# buck_chw_v3_0.net
KiCad netlist of a schematic drawn in Altium Designer
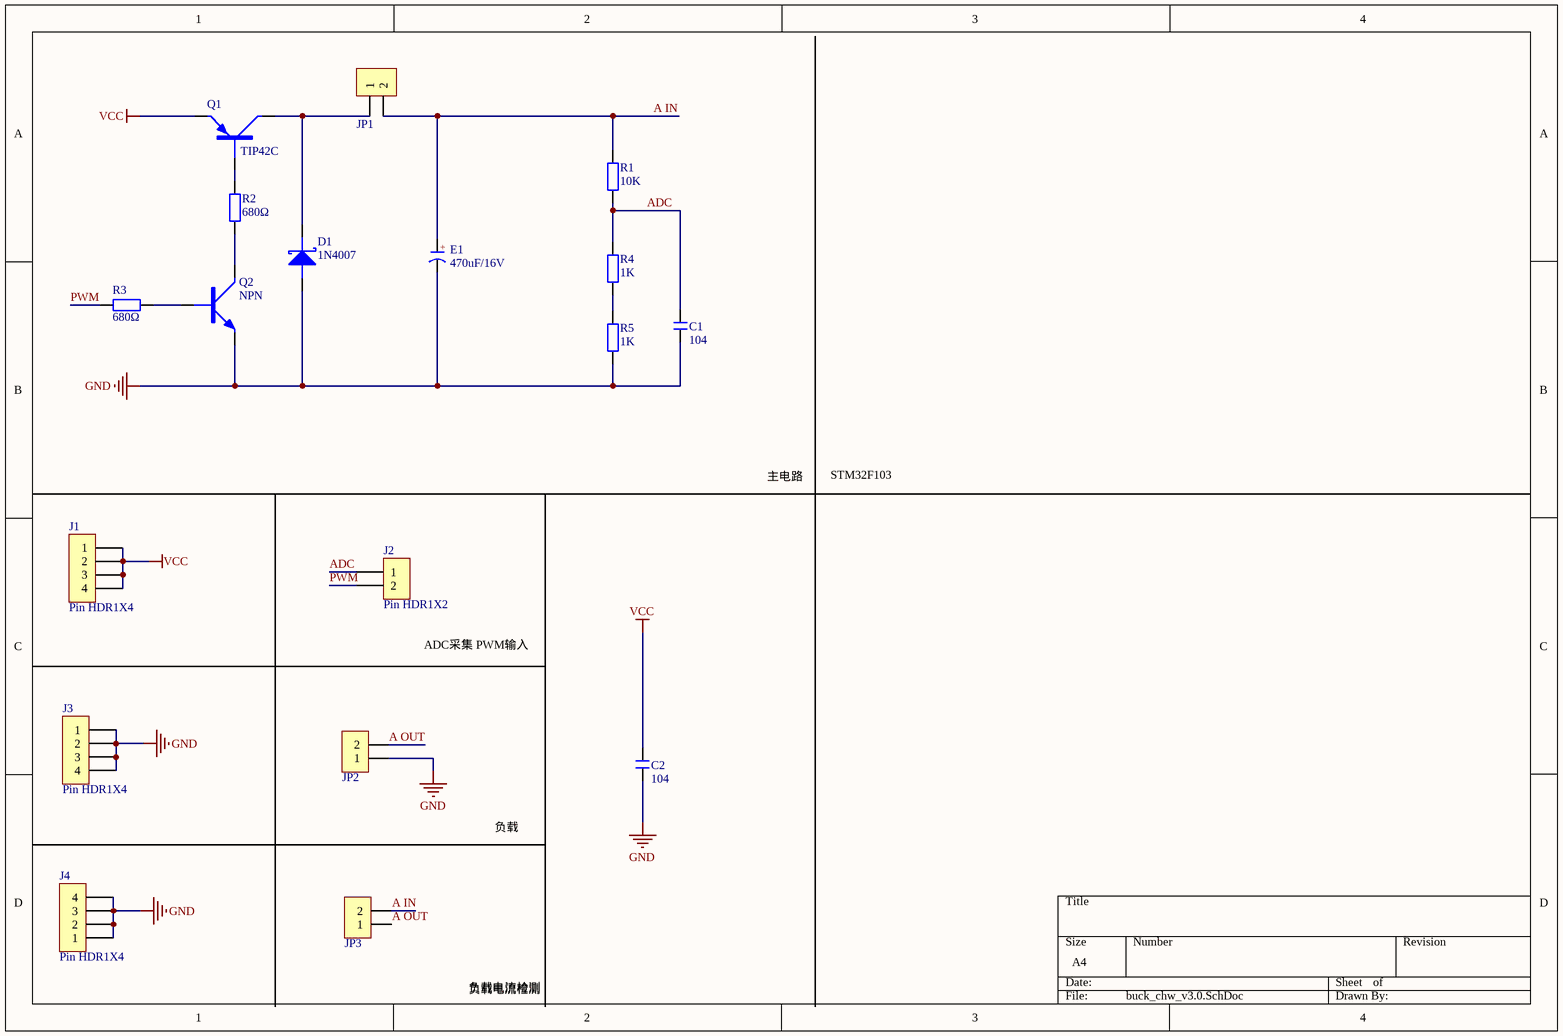
[diagram p0: buck_chw_v3.0.SchDoc]

(export (version "E")
  (design (tool "Eeschema 10.0.6"))
  (components
    (comp (ref "C1")
      (value "104")
      (footprint "CC 1.8*3.6")
      (description "直插瓷片电容")
      (fields (field (name "版权归属") "源创客"))
      (libsource (lib "3.1   - 电阻-电容-电感") (part "C-CC"))
    )
    (comp (ref "C2")
      (value "104")
      (footprint "CC 1.8*3.6")
      (description "直插瓷片电容")
      (fields (field (name "版权归属") "源创客"))
      (libsource (lib "3.1   - 电阻-电容-电感") (part "C-CC"))
    )
    (comp (ref "D1")
      (value "1N4007")
      (footprint "DO-15")
      (description "肖特基二极管")
      (libsource (lib "二极管") (part "DIODE SCHOTTKY"))
    )
    (comp (ref "E1")
      (value "470uF/16V")
      (footprint "CAP 1.5*4*8")
      (description "直插电解电容")
      (fields (field (name "版权归属") "源创客"))
      (libsource (lib "3.1   - 电阻-电容-电感") (part "C-CAP"))
    )
    (comp (ref "J1")
      (value "Pin HDR1X4")
      (footprint "Pin HDR1X4/2.54mm-S")
      (libsource (lib "") (part "Pin HDR1X4_1"))
    )
    (comp (ref "J2")
      (value "Pin HDR1X2")
      (footprint "Pin HDR1X2/2.54mm-S")
      (libsource (lib "排针") (part "Pin HDR1X2"))
    )
    (comp (ref "J3")
      (value "Pin HDR1X4")
      (footprint "Pin HDR1X4/2.54mm-S")
      (libsource (lib "") (part "Pin HDR1X4_1"))
    )
    (comp (ref "J4")
      (value "Pin HDR1X4")
      (footprint "Pin HDR1X4/2.54mm-S")
      (libsource (lib "排针") (part "Pin HDR1X4"))
    )
    (comp (ref "JP1")
      (value "HDR-1X2")
      (footprint "KF301-5.0-2P")
      (description "2P接插件")
      (fields (field (name "版权归属") "源创客"))
      (libsource (lib "") (part "Header 2_1"))
    )
    (comp (ref "JP2")
      (value "HDR-1X2")
      (footprint "KF301-5.0-2P")
      (description "2P接插件")
      (fields (field (name "版权归属") "源创客"))
      (libsource (lib "4.9   - 接插件-脚距5.0") (part "Header 2"))
    )
    (comp (ref "JP3")
      (value "HDR-1X2")
      (footprint "KF301-5.0-2P")
      (description "2P接插件")
      (fields (field (name "版权归属") "源创客"))
      (libsource (lib "4.9   - 接插件-脚距5.0") (part "Header 2"))
    )
    (comp (ref "Q1")
      (value "TIP42C")
      (footprint "Fe-HDR1X3/2.54-S")
      (description "PNP三极管")
      (libsource (lib "三极管") (part "PNP"))
    )
    (comp (ref "Q2")
      (value "NPN")
      (footprint "HDR2.54-Y-LI-3P")
      (description "NPN三极管")
      (libsource (lib "轻触开关") (part "NPN"))
    )
    (comp (ref "R1")
      (value "10K")
      (footprint "RS 1/4W")
      (description "直插色环电阻")
      (fields (field (name "版权归属") "源创客"))
      (libsource (lib "3.1   - 电阻-电容-电感") (part "R-CRR"))
    )
    (comp (ref "R2")
      (value "680Ω")
      (footprint "RS 1/4W")
      (description "直插色环电阻")
      (fields (field (name "版权归属") "源创客"))
      (libsource (lib "3.1   - 电阻-电容-电感") (part "R-CRR"))
    )
    (comp (ref "R3")
      (value "680Ω")
      (footprint "RS 1/4W")
      (description "直插色环电阻")
      (fields (field (name "版权归属") "源创客"))
      (libsource (lib "3.1   - 电阻-电容-电感") (part "R-CRR"))
    )
    (comp (ref "R4")
      (value "1K")
      (footprint "RS 1/4W")
      (description "直插色环电阻")
      (fields (field (name "版权归属") "源创客"))
      (libsource (lib "3.1   - 电阻-电容-电感") (part "R-CRR"))
    )
    (comp (ref "R5")
      (value "1K")
      (footprint "RS 1/4W")
      (description "直插色环电阻")
      (fields (field (name "版权归属") "源创客"))
      (libsource (lib "3.1   - 电阻-电容-电感") (part "R-CRR"))
    )
  )
  (nets
    (net (code "1") (name "/A IN") (class "Default")
      (node (ref "E1") (pin "1") (pinfunction "A_1") (pintype "passive"))
      (node (ref "JP1") (pin "2") (pinfunction "2_2") (pintype "passive"))
      (node (ref "JP3") (pin "2") (pinfunction "2_2") (pintype "passive"))
      (node (ref "R1") (pin "2") (pinfunction "2_2") (pintype "passive"))
    )
    (net (code "2") (name "/A OUT") (class "Default")
      (node (ref "JP2") (pin "2") (pinfunction "2_2") (pintype "passive"))
      (node (ref "JP3") (pin "1") (pinfunction "1_1") (pintype "passive"))
    )
    (net (code "3") (name "/ADC") (class "Default")
      (node (ref "C1") (pin "1") (pinfunction "1_1") (pintype "passive"))
      (node (ref "J2") (pin "1") (pinfunction "1_1") (pintype "passive"))
      (node (ref "R1") (pin "1") (pinfunction "1_1") (pintype "passive"))
      (node (ref "R4") (pin "2") (pinfunction "2_2") (pintype "passive"))
    )
    (net (code "4") (name "/PWM") (class "Default")
      (node (ref "J2") (pin "2") (pinfunction "2_2") (pintype "passive"))
      (node (ref "R3") (pin "1") (pinfunction "1_1") (pintype "passive"))
    )
    (net (code "5") (name "GND") (class "Default")
      (node (ref "C1") (pin "2") (pinfunction "2_2") (pintype "passive"))
      (node (ref "C2") (pin "2") (pinfunction "2_2") (pintype "passive"))
      (node (ref "D1") (pin "A") (pinfunction "A_A") (pintype "passive"))
      (node (ref "E1") (pin "2") (pinfunction "K_2") (pintype "passive"))
      (node (ref "J3") (pin "1") (pinfunction "1_1") (pintype "passive"))
      (node (ref "J3") (pin "2") (pinfunction "2_2") (pintype "passive"))
      (node (ref "J3") (pin "3") (pinfunction "3_3") (pintype "passive"))
      (node (ref "J3") (pin "4") (pinfunction "4_4") (pintype "passive"))
      (node (ref "J4") (pin "1") (pinfunction "1_1") (pintype "passive"))
      (node (ref "J4") (pin "2") (pinfunction "2_2") (pintype "passive"))
      (node (ref "J4") (pin "3") (pinfunction "3_3") (pintype "passive"))
      (node (ref "J4") (pin "4") (pinfunction "4_4") (pintype "passive"))
      (node (ref "JP2") (pin "1") (pinfunction "1_1") (pintype "passive"))
      (node (ref "Q2") (pin "E") (pinfunction "E_E") (pintype "passive"))
      (node (ref "R5") (pin "1") (pinfunction "1_1") (pintype "passive"))
    )
    (net (code "6") (name "Net-(D1-PadK)") (class "Default")
      (node (ref "D1") (pin "K") (pinfunction "K_K") (pintype "passive"))
      (node (ref "JP1") (pin "1") (pinfunction "1_1") (pintype "passive"))
      (node (ref "Q1") (pin "C") (pinfunction "C_C") (pintype "passive"))
    )
    (net (code "7") (name "Net-(Q1-PadB)") (class "Default")
      (node (ref "Q1") (pin "B") (pinfunction "B_B") (pintype "passive"))
      (node (ref "R2") (pin "2") (pinfunction "2_2") (pintype "passive"))
    )
    (net (code "8") (name "Net-(Q2-PadB)") (class "Default")
      (node (ref "Q2") (pin "B") (pinfunction "B_B") (pintype "passive"))
      (node (ref "R3") (pin "2") (pinfunction "2_2") (pintype "passive"))
    )
    (net (code "9") (name "Net-(Q2-PadC)") (class "Default")
      (node (ref "Q2") (pin "C") (pinfunction "C_C") (pintype "passive"))
      (node (ref "R2") (pin "1") (pinfunction "1_1") (pintype "passive"))
    )
    (net (code "10") (name "Net-(R4-Pad1)") (class "Default")
      (node (ref "R4") (pin "1") (pinfunction "1_1") (pintype "passive"))
      (node (ref "R5") (pin "2") (pinfunction "2_2") (pintype "passive"))
    )
    (net (code "11") (name "VCC") (class "Default")
      (node (ref "C2") (pin "1") (pinfunction "1_1") (pintype "passive"))
      (node (ref "J1") (pin "1") (pinfunction "1_1") (pintype "passive"))
      (node (ref "J1") (pin "2") (pinfunction "2_2") (pintype "passive"))
      (node (ref "J1") (pin "3") (pinfunction "3_3") (pintype "passive"))
      (node (ref "J1") (pin "4") (pinfunction "4_4") (pintype "passive"))
      (node (ref "Q1") (pin "E") (pinfunction "E_E") (pintype "passive"))
    )
  )
)
